# Arduino_Shield_v7_1_3.net
KiCad netlist of a schematic drawn in EAGLE
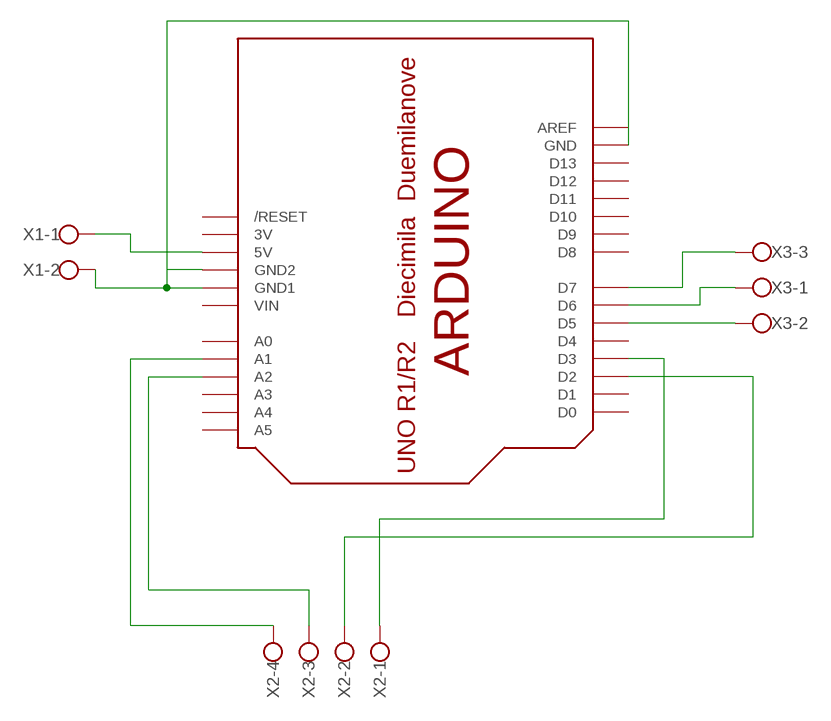
[diagram p0: schematic, sheet 1]

(export (version "E")
  (design (tool "Eeschema 10.0.6"))
  (components
    (comp (ref "U$1")
      (value "ARDUINOUNO")
      (footprint "eagle-import:ARDUINO")
      (libsource (lib "eagle-import") (part "ARDUINOUNO"))
    )
    (comp (ref "X1")
      (value "W237-102")
      (footprint "eagle-import:W237-102")
      (fields (field (name "MPN") "237-102"))
      (libsource (lib "eagle-import") (part "W237-102"))
    )
    (comp (ref "X2")
      (value "W237-4")
      (footprint "eagle-import:W237-4")
      (libsource (lib "eagle-import") (part "W237-4"))
    )
    (comp (ref "X3")
      (value "W237-103")
      (footprint "eagle-import:W237-103")
      (fields (field (name "MPN") "237-103"))
      (libsource (lib "eagle-import") (part "W237-103"))
    )
  )
  (nets
    (net (code "1") (name "/3V") (class "Default")
      (node (ref "U$1") (pin "3V") (pinfunction "3V_3V") (pintype "power_in"))
    )
    (net (code "2") (name "/VIN") (class "Default")
      (node (ref "U$1") (pin "VIN") (pinfunction "VIN_VIN") (pintype "power_in"))
    )
    (net (code "3") (name "Net-(X1A-KL)") (class "Default")
      (node (ref "U$1") (pin "5V") (pinfunction "5V_5V") (pintype "power_in"))
      (node (ref "X1") (pin "1") (pinfunction "KL_1") (pintype "passive"))
    )
    (net (code "4") (name "Net-(X1B-KL)") (class "Default")
      (node (ref "U$1") (pin "GND") (pinfunction "GND_GND") (pintype "power_in"))
      (node (ref "U$1") (pin "GND1") (pinfunction "GND1_GND1") (pintype "power_in"))
      (node (ref "U$1") (pin "GND2") (pinfunction "GND2_GND2") (pintype "power_in"))
      (node (ref "X1") (pin "2") (pinfunction "KL_2") (pintype "passive"))
    )
    (net (code "5") (name "Net-(X2A-KL)") (class "Default")
      (node (ref "U$1") (pin "D3") (pinfunction "D3_D3") (pintype "bidirectional"))
      (node (ref "X2") (pin "1") (pinfunction "KL_1") (pintype "passive"))
    )
    (net (code "6") (name "Net-(X2B-KL)") (class "Default")
      (node (ref "U$1") (pin "D2") (pinfunction "D2_D2") (pintype "bidirectional"))
      (node (ref "X2") (pin "2") (pinfunction "KL_2") (pintype "passive"))
    )
    (net (code "7") (name "Net-(X2C-KL)") (class "Default")
      (node (ref "U$1") (pin "A2") (pinfunction "A2_A2") (pintype "bidirectional"))
      (node (ref "X2") (pin "3") (pinfunction "KL_3") (pintype "passive"))
    )
    (net (code "8") (name "Net-(X2D-KL)") (class "Default")
      (node (ref "U$1") (pin "A1") (pinfunction "A1_A1") (pintype "bidirectional"))
      (node (ref "X2") (pin "4") (pinfunction "KL_4") (pintype "passive"))
    )
    (net (code "9") (name "Net-(X3A-KL)") (class "Default")
      (node (ref "U$1") (pin "D6") (pinfunction "D6_D6") (pintype "bidirectional"))
      (node (ref "X3") (pin "1") (pinfunction "KL_1") (pintype "passive"))
    )
    (net (code "10") (name "Net-(X3B-KL)") (class "Default")
      (node (ref "U$1") (pin "D5") (pinfunction "D5_D5") (pintype "bidirectional"))
      (node (ref "X3") (pin "2") (pinfunction "KL_2") (pintype "passive"))
    )
    (net (code "11") (name "Net-(X3C-KL)") (class "Default")
      (node (ref "U$1") (pin "D7") (pinfunction "D7_D7") (pintype "bidirectional"))
      (node (ref "X3") (pin "3") (pinfunction "KL_3") (pintype "passive"))
    )
    (net (code "12") (name "unconnected-(U$1-PadA0)") (class "Default")
      (node (ref "U$1") (pin "A0") (pinfunction "A0_A0") (pintype "bidirectional"))
    )
    (net (code "13") (name "unconnected-(U$1-PadA3)") (class "Default")
      (node (ref "U$1") (pin "A3") (pinfunction "A3_A3") (pintype "bidirectional"))
    )
    (net (code "14") (name "unconnected-(U$1-PadA4)") (class "Default")
      (node (ref "U$1") (pin "A4") (pinfunction "A4_A4") (pintype "bidirectional"))
    )
    (net (code "15") (name "unconnected-(U$1-PadA5)") (class "Default")
      (node (ref "U$1") (pin "A5") (pinfunction "A5_A5") (pintype "bidirectional"))
    )
    (net (code "16") (name "unconnected-(U$1-PadAREF)") (class "Default")
      (node (ref "U$1") (pin "AREF") (pinfunction "AREF_AREF") (pintype "bidirectional"))
    )
    (net (code "17") (name "unconnected-(U$1-PadD0)") (class "Default")
      (node (ref "U$1") (pin "D0") (pinfunction "D0_D0") (pintype "bidirectional"))
    )
    (net (code "18") (name "unconnected-(U$1-PadD1)") (class "Default")
      (node (ref "U$1") (pin "D1") (pinfunction "D1_D1") (pintype "bidirectional"))
    )
    (net (code "19") (name "unconnected-(U$1-PadD4)") (class "Default")
      (node (ref "U$1") (pin "D4") (pinfunction "D4_D4") (pintype "bidirectional"))
    )
    (net (code "20") (name "unconnected-(U$1-PadD8)") (class "Default")
      (node (ref "U$1") (pin "D8") (pinfunction "D8_D8") (pintype "bidirectional"))
    )
    (net (code "21") (name "unconnected-(U$1-PadD9)") (class "Default")
      (node (ref "U$1") (pin "D9") (pinfunction "D9_D9") (pintype "bidirectional"))
    )
    (net (code "22") (name "unconnected-(U$1-PadD10)") (class "Default")
      (node (ref "U$1") (pin "D10") (pinfunction "D10_D10") (pintype "bidirectional"))
    )
    (net (code "23") (name "unconnected-(U$1-PadD11)") (class "Default")
      (node (ref "U$1") (pin "D11") (pinfunction "D11_D11") (pintype "bidirectional"))
    )
    (net (code "24") (name "unconnected-(U$1-PadD12)") (class "Default")
      (node (ref "U$1") (pin "D12") (pinfunction "D12_D12") (pintype "bidirectional"))
    )
    (net (code "25") (name "unconnected-(U$1-PadD13)") (class "Default")
      (node (ref "U$1") (pin "D13") (pinfunction "D13_D13") (pintype "bidirectional"))
    )
    (net (code "26") (name "unconnected-(U$1-{slash}RESET-PadRESET)") (class "Default")
      (node (ref "U$1") (pin "RESET") (pinfunction "/RESET_RESET") (pintype "bidirectional"))
    )
  )
)
